# MCU.net
KiCad netlist of a schematic drawn in Altium Designer
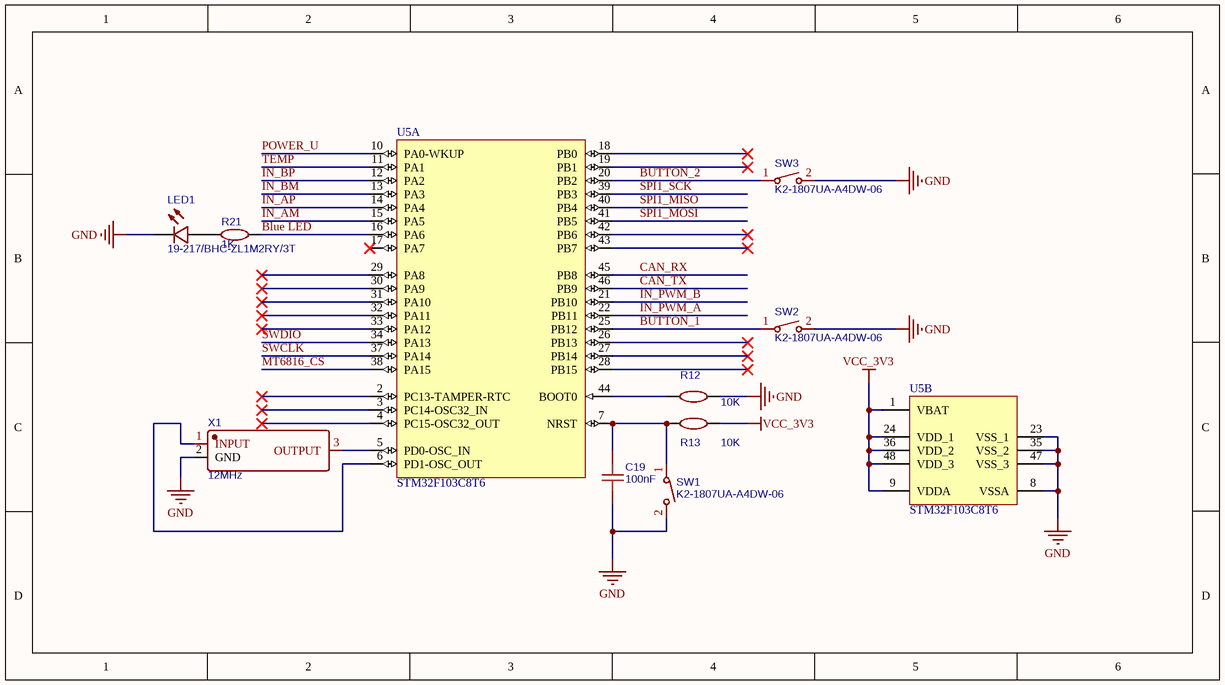
[diagram p0: MCU.SchDoc]

(export (version "E")
  (design (tool "Eeschema 10.0.6"))
  (components
    (comp (ref "C19")
      (value "100nF")
      (footprint "C0603")
      (fields
        (field (name "BOM_MANUFACTURER PART") "CL10B104KB8NNNC")
        (field (name "BOM_SUPPLIER PART") "C1591")
      )
      (libsource (lib "0.1uF") (part "100nF"))
    )
    (comp (ref "LED1")
      (value "19-217/BHC-ZL1M2RY/3T")
      (footprint "LED0603-R-RD_BLUE")
      (fields (field (name "BOM_SUPPLIER PART") "C72041"))
      (libsource (lib "Blue LED") (part "19-217/BHC-ZL1M2RY/3T"))
    )
    (comp (ref "R12")
      (value "10K")
      (footprint "R0603")
      (fields
        (field (name "BOM_MANUFACTURER PART") "0603WAF1002T5E")
        (field (name "BOM_SUPPLIER PART") "C25804")
      )
      (libsource (lib "10K") (part "10K"))
    )
    (comp (ref "R13")
      (value "10K")
      (footprint "R0603")
      (fields
        (field (name "BOM_MANUFACTURER PART") "0603WAF1002T5E")
        (field (name "BOM_SUPPLIER PART") "C25804")
      )
      (libsource (lib "10K") (part "10K"))
    )
    (comp (ref "R21")
      (value "1K")
      (footprint "R0603")
      (fields
        (field (name "BOM_MANUFACTURER PART") "0603WAF1001T5E")
        (field (name "BOM_SUPPLIER PART") "C21190")
      )
      (libsource (lib "1K") (part "1K"))
    )
    (comp (ref "SW1")
      (value "K2-1807UA-A4DW-06")
      (footprint "KEY-SMD_L4.0-W2.9-L")
      (fields (field (name "BOM_SUPPLIER PART") "C502307") (field (name "CONTRIBUTOR") "LCSC"))
      (libsource (lib "BUTTON") (part "K2-1807UA-A4DW-06"))
    )
    (comp (ref "SW2")
      (value "K2-1807UA-A4DW-06")
      (footprint "KEY-SMD_L4.0-W2.9-L")
      (fields (field (name "BOM_SUPPLIER PART") "C502307") (field (name "CONTRIBUTOR") "LCSC"))
      (libsource (lib "BUTTON") (part "K2-1807UA-A4DW-06"))
    )
    (comp (ref "SW3")
      (value "K2-1807UA-A4DW-06")
      (footprint "KEY-SMD_L4.0-W2.9-L")
      (fields (field (name "BOM_SUPPLIER PART") "C502307") (field (name "CONTRIBUTOR") "LCSC"))
      (libsource (lib "BUTTON") (part "K2-1807UA-A4DW-06"))
    )
    (comp (ref "U5")
      (value "STM32F103C8T6")
      (footprint "STM-LQFP48_L")
      (libsource (lib "Altium Content Vault") (part "MC-ARM-STM32F103X8_B-SQ48"))
    )
    (comp (ref "X1")
      (value "12MHz")
      (footprint "CRYSTAL-SMD_3P-L3.2-W1.3-P1.2-BL")
      (fields
        (field (name "BOM_SUPPLIER PART") "C907957")
        (field (name "BOM_MANUFACTURER PART") "CSTNE12M0G52A000R0")
        (field (name "CONTRIBUTOR") "LCSC")
      )
      (libsource (lib "12MHZ CUNTIAN") (part "12MHz"))
    )
  )
  (nets
    (net (code "1") (name "/BUTTON_1") (class "Default")
      (node (ref "SW2") (pin "1") (pinfunction "1_1") (pintype "passive"))
      (node (ref "U5") (pin "25") (pinfunction "PB12_25") (pintype "bidirectional"))
    )
    (net (code "2") (name "/BUTTON_2") (class "Default")
      (node (ref "SW3") (pin "1") (pinfunction "1_1") (pintype "passive"))
      (node (ref "U5") (pin "20") (pinfunction "PB2_20") (pintype "bidirectional"))
    )
    (net (code "3") (name "/Blue LED") (class "Default")
      (node (ref "R21") (pin "2") (pinfunction "2_2") (pintype "passive"))
      (node (ref "U5") (pin "16") (pinfunction "PA6_16") (pintype "bidirectional"))
    )
    (net (code "4") (name "/CAN_RX") (class "Default")
      (node (ref "U5") (pin "45") (pinfunction "PB8_45") (pintype "bidirectional"))
    )
    (net (code "5") (name "/CAN_TX") (class "Default")
      (node (ref "U5") (pin "46") (pinfunction "PB9_46") (pintype "bidirectional"))
    )
    (net (code "6") (name "/IN_AM") (class "Default")
      (node (ref "U5") (pin "15") (pinfunction "PA5_15") (pintype "bidirectional"))
    )
    (net (code "7") (name "/IN_AP") (class "Default")
      (node (ref "U5") (pin "14") (pinfunction "PA4_14") (pintype "bidirectional"))
    )
    (net (code "8") (name "/IN_BM") (class "Default")
      (node (ref "U5") (pin "13") (pinfunction "PA3_13") (pintype "bidirectional"))
    )
    (net (code "9") (name "/IN_BP") (class "Default")
      (node (ref "U5") (pin "12") (pinfunction "PA2_12") (pintype "bidirectional"))
    )
    (net (code "10") (name "/IN_PWM_A") (class "Default")
      (node (ref "U5") (pin "22") (pinfunction "PB11_22") (pintype "bidirectional"))
    )
    (net (code "11") (name "/IN_PWM_B") (class "Default")
      (node (ref "U5") (pin "21") (pinfunction "PB10_21") (pintype "bidirectional"))
    )
    (net (code "12") (name "/MT6816_CS") (class "Default")
      (node (ref "U5") (pin "38") (pinfunction "PA15_38") (pintype "bidirectional"))
    )
    (net (code "13") (name "/POWER_U") (class "Default")
      (node (ref "U5") (pin "10") (pinfunction "PA0-WKUP_10") (pintype "bidirectional"))
    )
    (net (code "14") (name "/SPI1_MISO") (class "Default")
      (node (ref "U5") (pin "40") (pinfunction "PB4_40") (pintype "bidirectional"))
    )
    (net (code "15") (name "/SPI1_MOSI") (class "Default")
      (node (ref "U5") (pin "41") (pinfunction "PB5_41") (pintype "bidirectional"))
    )
    (net (code "16") (name "/SPI1_SCK") (class "Default")
      (node (ref "U5") (pin "39") (pinfunction "PB3_39") (pintype "bidirectional"))
    )
    (net (code "17") (name "/SWCLK") (class "Default")
      (node (ref "U5") (pin "37") (pinfunction "PA14_37") (pintype "bidirectional"))
    )
    (net (code "18") (name "/SWDIO") (class "Default")
      (node (ref "U5") (pin "34") (pinfunction "PA13_34") (pintype "bidirectional"))
    )
    (net (code "19") (name "/TEMP") (class "Default")
      (node (ref "U5") (pin "11") (pinfunction "PA1_11") (pintype "bidirectional"))
    )
    (net (code "20") (name "GND") (class "Default")
      (node (ref "C19") (pin "1") (pinfunction "1_1") (pintype "passive"))
      (node (ref "LED1") (pin "2") (pinfunction "C_2") (pintype "passive"))
      (node (ref "R12") (pin "2") (pinfunction "2_2") (pintype "passive"))
      (node (ref "SW1") (pin "2") (pinfunction "2_2") (pintype "passive"))
      (node (ref "SW2") (pin "2") (pinfunction "2_2") (pintype "passive"))
      (node (ref "SW3") (pin "2") (pinfunction "2_2") (pintype "passive"))
      (node (ref "U5") (pin "23") (pinfunction "VSS_1_23") (pintype "power_in"))
      (node (ref "U5") (pin "35") (pinfunction "VSS_2_35") (pintype "power_in"))
      (node (ref "U5") (pin "47") (pinfunction "VSS_3_47") (pintype "power_in"))
      (node (ref "U5") (pin "8") (pinfunction "VSSA_8") (pintype "power_in"))
      (node (ref "X1") (pin "2") (pinfunction "GND_2") (pintype "passive"))
    )
    (net (code "21") (name "Net-(LED1-A)") (class "Default")
      (node (ref "LED1") (pin "1") (pinfunction "A_1") (pintype "passive"))
      (node (ref "R21") (pin "1") (pinfunction "1_1") (pintype "passive"))
    )
    (net (code "22") (name "Net-(U5A-BOOT0)") (class "Default")
      (node (ref "R12") (pin "1") (pinfunction "1_1") (pintype "passive"))
      (node (ref "U5") (pin "44") (pinfunction "BOOT0_44") (pintype "input"))
    )
    (net (code "23") (name "Net-(U5A-NRST)") (class "Default")
      (node (ref "C19") (pin "2") (pinfunction "2_2") (pintype "passive"))
      (node (ref "R13") (pin "1") (pinfunction "1_1") (pintype "passive"))
      (node (ref "SW1") (pin "1") (pinfunction "1_1") (pintype "passive"))
      (node (ref "U5") (pin "7") (pinfunction "NRST_7") (pintype "bidirectional"))
    )
    (net (code "24") (name "Net-(U5A-PD0-OSC_IN)") (class "Default")
      (node (ref "U5") (pin "5") (pinfunction "PD0-OSC_IN_5") (pintype "bidirectional"))
      (node (ref "X1") (pin "3") (pinfunction "OUTPUT_3") (pintype "passive"))
    )
    (net (code "25") (name "Net-(U5A-PD1-OSC_OUT)") (class "Default")
      (node (ref "U5") (pin "6") (pinfunction "PD1-OSC_OUT_6") (pintype "bidirectional"))
      (node (ref "X1") (pin "1") (pinfunction "INPUT_1") (pintype "passive"))
    )
    (net (code "26") (name "VCC_3V3") (class "Default")
      (node (ref "R13") (pin "2") (pinfunction "2_2") (pintype "passive"))
      (node (ref "U5") (pin "1") (pinfunction "VBAT_1") (pintype "power_in"))
      (node (ref "U5") (pin "24") (pinfunction "VDD_1_24") (pintype "power_in"))
      (node (ref "U5") (pin "36") (pinfunction "VDD_2_36") (pintype "power_in"))
      (node (ref "U5") (pin "48") (pinfunction "VDD_3_48") (pintype "power_in"))
      (node (ref "U5") (pin "9") (pinfunction "VDDA_9") (pintype "power_in"))
    )
    (net (code "27") (name "unconnected-(U5A-PA7-Pad17)") (class "Default")
      (node (ref "U5") (pin "17") (pinfunction "PA7_17") (pintype "bidirectional+no_connect"))
    )
    (net (code "28") (name "unconnected-(U5A-PA8-Pad29)") (class "Default")
      (node (ref "U5") (pin "29") (pinfunction "PA8_29") (pintype "bidirectional+no_connect"))
    )
    (net (code "29") (name "unconnected-(U5A-PA9-Pad30)") (class "Default")
      (node (ref "U5") (pin "30") (pinfunction "PA9_30") (pintype "bidirectional+no_connect"))
    )
    (net (code "30") (name "unconnected-(U5A-PA10-Pad31)") (class "Default")
      (node (ref "U5") (pin "31") (pinfunction "PA10_31") (pintype "bidirectional+no_connect"))
    )
    (net (code "31") (name "unconnected-(U5A-PA11-Pad32)") (class "Default")
      (node (ref "U5") (pin "32") (pinfunction "PA11_32") (pintype "bidirectional+no_connect"))
    )
    (net (code "32") (name "unconnected-(U5A-PA12-Pad33)") (class "Default")
      (node (ref "U5") (pin "33") (pinfunction "PA12_33") (pintype "bidirectional+no_connect"))
    )
    (net (code "33") (name "unconnected-(U5A-PB0-Pad18)") (class "Default")
      (node (ref "U5") (pin "18") (pinfunction "PB0_18") (pintype "bidirectional+no_connect"))
    )
    (net (code "34") (name "unconnected-(U5A-PB1-Pad19)") (class "Default")
      (node (ref "U5") (pin "19") (pinfunction "PB1_19") (pintype "bidirectional+no_connect"))
    )
    (net (code "35") (name "unconnected-(U5A-PB6-Pad42)") (class "Default")
      (node (ref "U5") (pin "42") (pinfunction "PB6_42") (pintype "bidirectional+no_connect"))
    )
    (net (code "36") (name "unconnected-(U5A-PB7-Pad43)") (class "Default")
      (node (ref "U5") (pin "43") (pinfunction "PB7_43") (pintype "bidirectional+no_connect"))
    )
    (net (code "37") (name "unconnected-(U5A-PB13-Pad26)") (class "Default")
      (node (ref "U5") (pin "26") (pinfunction "PB13_26") (pintype "bidirectional+no_connect"))
    )
    (net (code "38") (name "unconnected-(U5A-PB14-Pad27)") (class "Default")
      (node (ref "U5") (pin "27") (pinfunction "PB14_27") (pintype "bidirectional+no_connect"))
    )
    (net (code "39") (name "unconnected-(U5A-PB15-Pad28)") (class "Default")
      (node (ref "U5") (pin "28") (pinfunction "PB15_28") (pintype "bidirectional+no_connect"))
    )
    (net (code "40") (name "unconnected-(U5A-PC13-TAMPER-RTC-Pad2)") (class "Default")
      (node (ref "U5") (pin "2") (pinfunction "PC13-TAMPER-RTC_2") (pintype "bidirectional+no_connect"))
    )
    (net (code "41") (name "unconnected-(U5A-PC14-OSC32_IN-Pad3)") (class "Default")
      (node (ref "U5") (pin "3") (pinfunction "PC14-OSC32_IN_3") (pintype "bidirectional+no_connect"))
    )
    (net (code "42") (name "unconnected-(U5A-PC15-OSC32_OUT-Pad4)") (class "Default")
      (node (ref "U5") (pin "4") (pinfunction "PC15-OSC32_OUT_4") (pintype "bidirectional+no_connect"))
    )
  )
)
